# pca10028_connectors.net
KiCad netlist of a schematic drawn in Altium Designer
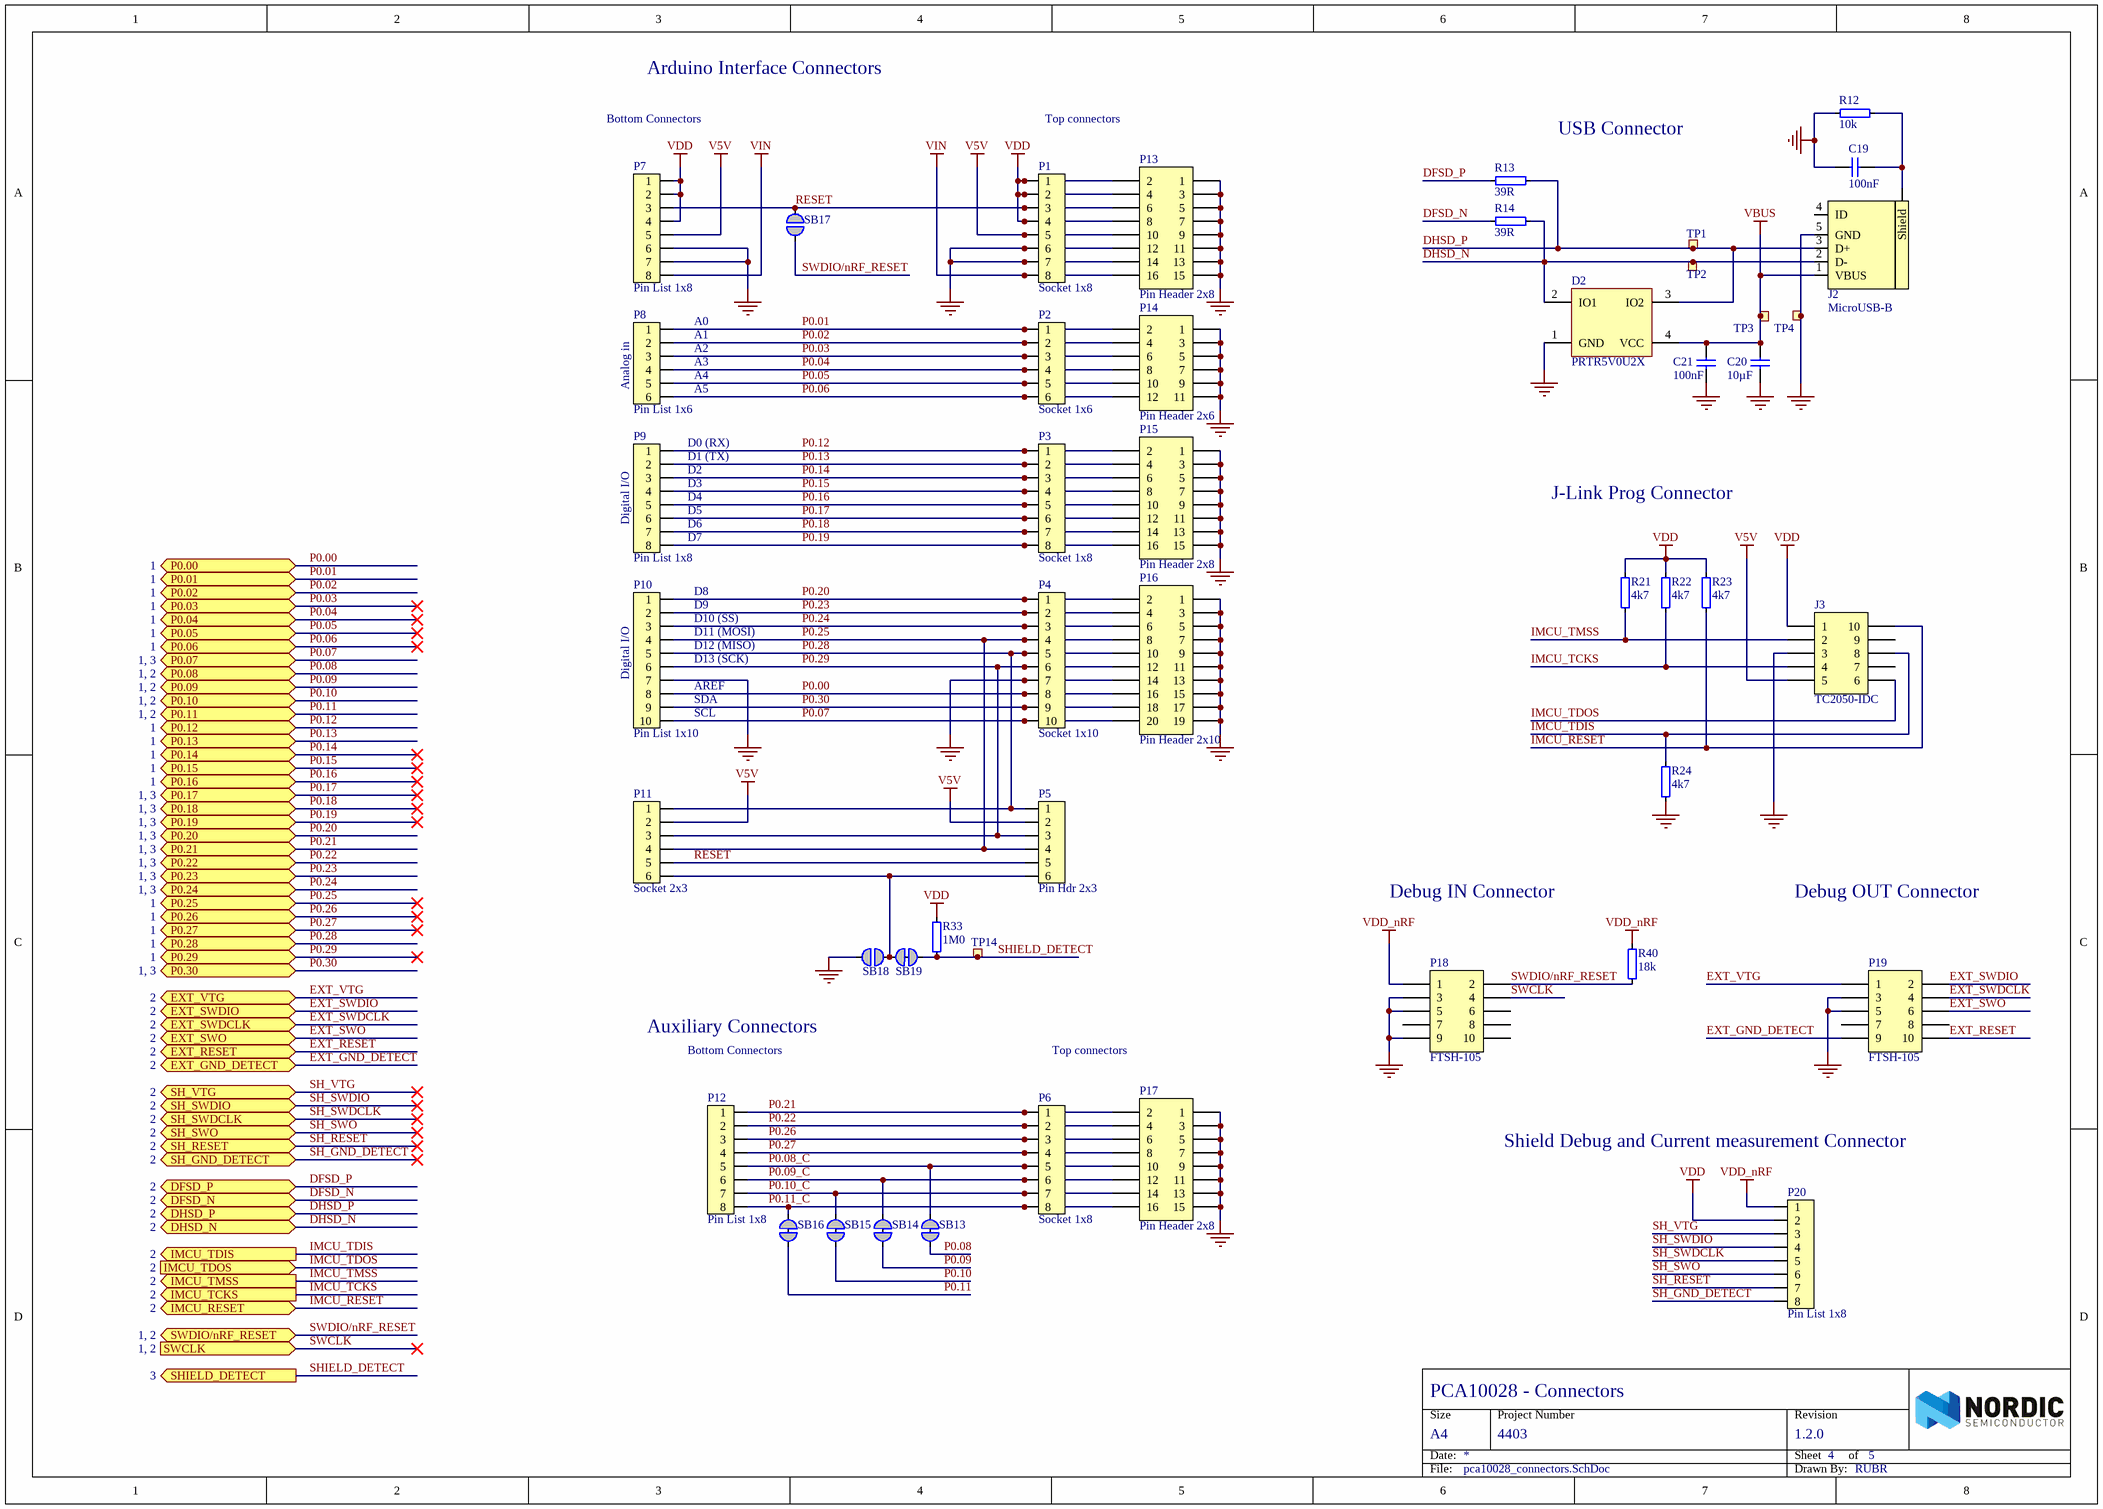
[diagram p0: pca10028_connectors.SchDoc]

(export (version "E")
  (design (tool "Eeschema 10.0.6"))
  (components
    (comp (ref "C19")
      (value "100nF")
      (footprint "CAPC1005X04L")
      (description "Capacitor, X7R, ±10%")
      (fields (field (name "PART NUMBER") "C0402-100n") (field (name "PUBLISHER") "Nordic Semiconductor"))
      (libsource (lib "Nordic Passive DB") (part "CAP"))
    )
    (comp (ref "C20")
      (value "10µF")
      (footprint "CAPC1608X06L")
      (description "Capacitor, X5R, ±20%")
      (fields (field (name "PART NUMBER") "C0603-10µ") (field (name "PUBLISHER") "Nordic Semiconductor"))
      (libsource (lib "Nordic Passive DB") (part "CAP"))
    )
    (comp (ref "C21")
      (value "100nF")
      (footprint "CAPC1005X04L")
      (description "Capacitor, X7R, ±10%")
      (fields (field (name "PART NUMBER") "C0402-100n") (field (name "PUBLISHER") "Nordic Semiconductor"))
      (libsource (lib "Nordic Passive DB") (part "CAP"))
    )
    (comp (ref "D2")
      (value "PRTR5V0U2X")
      (footprint "SOT190P230X110-4L")
      (description "Ultra low capacitance double rail-to-rail ESD protection diode")
      (fields
        (field (name "MANUFACTURER") "NXP")
        (field (name "2ND SOURCE PART NUMBER") "152-4157")
        (field (name "PUBLISHER") "Nordic Semiconductor")
      )
      (libsource (lib "Nordic Discrete DB") (part "PRTR5V0U2X"))
    )
    (comp (ref "J2")
      (value "MicroUSB-B")
      (footprint "FCI_10118193-0001LF")
      (description "MicroUSB-B-SMT")
      (fields
        (field (name "PART NUMBER") "FCI 10118193-0001LF")
        (field (name "MANUFACTURER") "FCI")
        (field (name "PUBLISHER") "Nordic Semiconductor")
      )
      (libsource (lib "Nordic Passive DB") (part "MiniUSB-AB-SMT"))
    )
    (comp (ref "J3")
      (value "TC2050-IDC")
      (footprint "TC2050-IDC-NLFP")
      (description "CBL PLUG-OF-NAILS 10-PIN")
      (fields
        (field (name "PART NUMBER") "TC2050-IDC-NLFP")
        (field (name "MANUFACTURER") "Tag-Connect LLC")
        (field (name "PUBLISHER") "Nordic Semiconductor")
      )
      (libsource (lib "Nordic Passive DB") (part "CONN-2x5_var2"))
    )
    (comp (ref "P1")
      (value "Socket 1x8")
      (footprint "SOCKET_1x8_SMD")
      (description "Socket 1x8, 2.54mm (100mil), SMD")
      (fields
        (field (name "PART NUMBER") "Socket 1x8 SMD")
        (field (name "MANUFACTURER") "Samtec")
        (field (name "PUBLISHER") "Nordic Semiconductor")
      )
      (libsource (lib "Nordic Passive DB") (part "CONN-8"))
    )
    (comp (ref "P2")
      (value "Socket 1x6")
      (footprint "SOCKET_1x6_SMD")
      (description "Socket 1x6, 2.54mm (100mil), SMD")
      (fields
        (field (name "PART NUMBER") "Socket 1x6 SMD")
        (field (name "MANUFACTURER") "Samtec")
        (field (name "PUBLISHER") "Nordic Semiconductor")
      )
      (libsource (lib "Nordic Passive DB") (part "CONN-6"))
    )
    (comp (ref "P3")
      (value "Socket 1x8")
      (footprint "SOCKET_1x8_SMD")
      (description "Socket 1x8, 2.54mm (100mil), SMD")
      (fields
        (field (name "PART NUMBER") "Socket 1x8 SMD")
        (field (name "MANUFACTURER") "Samtec")
        (field (name "PUBLISHER") "Nordic Semiconductor")
      )
      (libsource (lib "Nordic Passive DB") (part "CONN-8"))
    )
    (comp (ref "P4")
      (value "Socket 1x10")
      (footprint "SOCKET_1x10_SMD")
      (description "Socket 1x10, 2.54mm (100mil), SMD")
      (fields
        (field (name "PART NUMBER") "Socket 1x10 SMD")
        (field (name "MANUFACTURER") "Samtec")
        (field (name "PUBLISHER") "Nordic Semiconductor")
      )
      (libsource (lib "Nordic Passive DB") (part "CONN-10"))
    )
    (comp (ref "P5")
      (value "Pin Hdr 2x3")
      (footprint "Molex 15-91-2060")
      (description "Pin Header 2x3, 2.54mm (100mil) SMD")
      (fields
        (field (name "PART NUMBER") "Pin Header 2x3 SMD")
        (field (name "MANUFACTURER") "Molex")
        (field (name "PUBLISHER") "Nordic Semiconductor")
      )
      (libsource (lib "Nordic Passive DB") (part "CONN-6"))
    )
    (comp (ref "P6")
      (value "Socket 1x8")
      (footprint "SOCKET_1x8_SMD")
      (description "Socket 1x8, 2.54mm (100mil), SMD")
      (fields
        (field (name "PART NUMBER") "Socket 1x8 SMD")
        (field (name "MANUFACTURER") "Samtec")
        (field (name "PUBLISHER") "Nordic Semiconductor")
      )
      (libsource (lib "Nordic Passive DB") (part "CONN-8"))
    )
    (comp (ref "P7")
      (value "Pin List 1x8")
      (footprint "LIST_1x8_SMD")
      (description "Pin List 1x8, 2.54mm (100mil), SMD")
      (fields
        (field (name "PART NUMBER") "Pin List 1x8 SMD")
        (field (name "PUBLISHER") "Nordic Semiconductor")
      )
      (libsource (lib "") (part "CONN-8_1"))
    )
    (comp (ref "P8")
      (value "Pin List 1x6")
      (footprint "LIST_1x6_SMD")
      (description "Pin List 1x6, 2.54mm (100mil), SMD")
      (fields
        (field (name "PART NUMBER") "Pin List 1x6 SMD")
        (field (name "PUBLISHER") "Nordic Semiconductor")
      )
      (libsource (lib "") (part "CONN-6_1"))
    )
    (comp (ref "P9")
      (value "Pin List 1x8")
      (footprint "LIST_1x8_SMD")
      (description "Pin List 1x8, 2.54mm (100mil), SMD")
      (fields
        (field (name "PART NUMBER") "Pin List 1x8 SMD")
        (field (name "PUBLISHER") "Nordic Semiconductor")
      )
      (libsource (lib "") (part "CONN-8_1"))
    )
    (comp (ref "P10")
      (value "Pin List 1x10")
      (footprint "LIST_1x10_SMD")
      (description "Pin List 1x10, 2.54mm (100mil), SMD")
      (fields
        (field (name "PART NUMBER") "Pin List 1x10 SMD")
        (field (name "PUBLISHER") "Nordic Semiconductor")
      )
      (libsource (lib "") (part "CONN-10_1"))
    )
    (comp (ref "P11")
      (value "Socket 2x3")
      (footprint "SOCKET_2x3_SMD-2.54mm-bottom")
      (description "Socket 2x3, 2.54mm (100mil), SMD")
      (fields
        (field (name "PART NUMBER") "Socket 2x3 SMD Bottom")
        (field (name "MANUFACTURER") "Samtec")
        (field (name "PUBLISHER") "Nordic Semiconductor")
      )
      (libsource (lib "") (part "CONN-6_1"))
    )
    (comp (ref "P12")
      (value "Pin List 1x8")
      (footprint "LIST_1x8_SMD")
      (description "Pin List 1x8, 2.54mm (100mil), SMD")
      (fields
        (field (name "PART NUMBER") "Pin List 1x8 SMD")
        (field (name "PUBLISHER") "Nordic Semiconductor")
      )
      (libsource (lib "") (part "CONN-8_1"))
    )
    (comp (ref "P13")
      (value "Pin Header 2x8")
      (footprint "HDR_2x8")
      (description "Pin Header 2x8, 2.54mm (100mil)")
      (fields (field (name "PUBLISHER") "Nordic Semiconductor"))
      (libsource (lib "Nordic Passive DB") (part "CONN-2x8"))
    )
    (comp (ref "P14")
      (value "Pin Header 2x6")
      (footprint "HDR_2x6")
      (description "Pin Header 2x6, 2.54mm (100mil)")
      (fields (field (name "PUBLISHER") "Nordic Semiconductor"))
      (libsource (lib "Nordic Passive DB") (part "CONN-2x6"))
    )
    (comp (ref "P15")
      (value "Pin Header 2x8")
      (footprint "HDR_2x8")
      (description "Pin Header 2x8, 2.54mm (100mil)")
      (fields (field (name "PUBLISHER") "Nordic Semiconductor"))
      (libsource (lib "Nordic Passive DB") (part "CONN-2x8"))
    )
    (comp (ref "P16")
      (value "Pin Header 2x10")
      (footprint "HDR_2x10")
      (description "Pin Header 2x10, 2.54mm (100mil)")
      (fields (field (name "PUBLISHER") "Nordic Semiconductor"))
      (libsource (lib "Nordic Passive DB") (part "CONN-2x10"))
    )
    (comp (ref "P17")
      (value "Pin Header 2x8")
      (footprint "HDR_2x8")
      (description "Pin Header 2x8, 2.54mm (100mil)")
      (fields (field (name "PUBLISHER") "Nordic Semiconductor"))
      (libsource (lib "Nordic Passive DB") (part "CONN-2x8"))
    )
    (comp (ref "P18")
      (value "FTSH-105")
      (footprint "FTSH-105-K")
      (description "SAMTEC - CONN HEADER 10POS DUAL .05\" SMD KEYING SHROUD")
      (fields
        (field (name "PART NUMBER") "Samtec FTSH-105 Keying Shroud")
        (field (name "MANUFACTURER") "Samtec")
        (field (name "PUBLISHER") "Nordic Semiconductor")
      )
      (libsource (lib "Nordic Passive DB") (part "CONN-2x5"))
    )
    (comp (ref "P19")
      (value "FTSH-105")
      (footprint "FTSH-105-K")
      (description "SAMTEC - CONN HEADER 10POS DUAL .05\" SMD KEYING SHROUD")
      (fields
        (field (name "PART NUMBER") "Samtec FTSH-105 Keying Shroud")
        (field (name "MANUFACTURER") "Samtec")
        (field (name "PUBLISHER") "Nordic Semiconductor")
      )
      (libsource (lib "Nordic Passive DB") (part "CONN-2x5"))
    )
    (comp (ref "P20")
      (value "Pin List 1x8")
      (footprint "LIST_1x8_SMD")
      (description "Pin List 1x8, 2.54mm (100mil), SMD")
      (fields
        (field (name "PART NUMBER") "Pin List 1x8 SMD")
        (field (name "PUBLISHER") "Nordic Semiconductor")
      )
      (libsource (lib "Nordic Passive DB") (part "CONN-8"))
    )
    (comp (ref "R12")
      (value "10k")
      (footprint "RESC1005X04L")
      (description "Resistor, ±1%, 0.063W")
      (fields (field (name "PART NUMBER") "R0402-10k") (field (name "PUBLISHER") "Nordic Semiconductor"))
      (libsource (lib "Nordic Passive DB") (part "RES_1"))
    )
    (comp (ref "R13")
      (value "39R")
      (footprint "RESC1005X04L")
      (description "Resistor, ±1%, 0.063W")
      (fields (field (name "PART NUMBER") "R0402-39R") (field (name "PUBLISHER") "Nordic Semiconductor"))
      (libsource (lib "Nordic Passive DB") (part "RES_1"))
    )
    (comp (ref "R14")
      (value "39R")
      (footprint "RESC1005X04L")
      (description "Resistor, ±1%, 0.063W")
      (fields (field (name "PART NUMBER") "R0402-39R") (field (name "PUBLISHER") "Nordic Semiconductor"))
      (libsource (lib "Nordic Passive DB") (part "RES_1"))
    )
    (comp (ref "R21")
      (value "4k7")
      (footprint "RESC1005X04L")
      (description "Resistor, ±1%, 0.063W")
      (fields (field (name "PART NUMBER") "R0402-4k7") (field (name "PUBLISHER") "Nordic Semiconductor"))
      (libsource (lib "Nordic Passive DB") (part "RES_1"))
    )
    (comp (ref "R22")
      (value "4k7")
      (footprint "RESC1005X04L")
      (description "Resistor, ±1%, 0.063W")
      (fields (field (name "PART NUMBER") "R0402-4k7") (field (name "PUBLISHER") "Nordic Semiconductor"))
      (libsource (lib "Nordic Passive DB") (part "RES_1"))
    )
    (comp (ref "R23")
      (value "4k7")
      (footprint "RESC1005X04L")
      (description "Resistor, ±1%, 0.063W")
      (fields (field (name "PART NUMBER") "R0402-4k7") (field (name "PUBLISHER") "Nordic Semiconductor"))
      (libsource (lib "Nordic Passive DB") (part "RES_1"))
    )
    (comp (ref "R24")
      (value "4k7")
      (footprint "RESC1005X04L")
      (description "Resistor, ±1%, 0.063W")
      (fields (field (name "PART NUMBER") "R0402-4k7") (field (name "PUBLISHER") "Nordic Semiconductor"))
      (libsource (lib "Nordic Passive DB") (part "RES_1"))
    )
    (comp (ref "R33")
      (value "1M0")
      (footprint "RESC1005X04L")
      (description "Resistor, ±1%, 0.063W")
      (fields (field (name "PART NUMBER") "R0402-1M0") (field (name "PUBLISHER") "Nordic Semiconductor"))
      (libsource (lib "Nordic Passive DB") (part "RES_1"))
    )
    (comp (ref "R40")
      (value "18k")
      (footprint "RESC1005X04L")
      (description "Resistor, ±1%, 0.063W")
      (fields (field (name "PART NUMBER") "R0402-18k") (field (name "PUBLISHER") "Nordic Semiconductor"))
      (libsource (lib "Nordic Passive DB") (part "RES_1"))
    )
    (comp (ref "SB13")
      (value "Solderbridge")
      (footprint "Solderbridge_Shorted")
      (description "Shorted Solderbridge")
      (fields
        (field (name "PART NUMBER") "Solderbridge Shorted")
        (field (name "PUBLISHER") "Nordic Semiconductor")
      )
      (libsource (lib "Nordic Passive DB") (part "SOLDERBRIDGE_SHORTED"))
    )
    (comp (ref "SB14")
      (value "Solderbridge")
      (footprint "Solderbridge_Shorted")
      (description "Shorted Solderbridge")
      (fields
        (field (name "PART NUMBER") "Solderbridge Shorted")
        (field (name "PUBLISHER") "Nordic Semiconductor")
      )
      (libsource (lib "Nordic Passive DB") (part "SOLDERBRIDGE_SHORTED"))
    )
    (comp (ref "SB15")
      (value "Solderbridge")
      (footprint "Solderbridge_Shorted")
      (description "Shorted Solderbridge")
      (fields
        (field (name "PART NUMBER") "Solderbridge Shorted")
        (field (name "PUBLISHER") "Nordic Semiconductor")
      )
      (libsource (lib "Nordic Passive DB") (part "SOLDERBRIDGE_SHORTED"))
    )
    (comp (ref "SB16")
      (value "Solderbridge")
      (footprint "Solderbridge_Shorted")
      (description "Shorted Solderbridge")
      (fields
        (field (name "PART NUMBER") "Solderbridge Shorted")
        (field (name "PUBLISHER") "Nordic Semiconductor")
      )
      (libsource (lib "Nordic Passive DB") (part "SOLDERBRIDGE_SHORTED"))
    )
    (comp (ref "SB17")
      (value "Solderbridge")
      (footprint "Solderbridge")
      (fields (field (name "PUBLISHER") "Nordic Semiconductor"))
      (libsource (lib "Nordic Passive DB") (part "SOLDERBRIDGE"))
    )
    (comp (ref "SB18")
      (value "Solderbridge")
      (footprint "Solderbridge")
      (fields (field (name "PUBLISHER") "Nordic Semiconductor"))
      (libsource (lib "Nordic Passive DB") (part "SOLDERBRIDGE"))
    )
    (comp (ref "SB19")
      (value "Solderbridge")
      (footprint "Solderbridge_Shorted")
      (description "Shorted Solderbridge")
      (fields
        (field (name "PART NUMBER") "Solderbridge Shorted")
        (field (name "PUBLISHER") "Nordic Semiconductor")
      )
      (libsource (lib "Nordic Passive DB") (part "SOLDERBRIDGE_SHORTED"))
    )
    (comp (ref "TP1")
      (value "Ø1.0mm,SMD")
      (footprint "TP_SMD_Ø1.0mm")
      (description "1.0mm circular SMD testpad")
      (fields
        (field (name "PART NUMBER") "TP_SMD_Ø1.0MM")
        (field (name "MANUFACTURER") "Nordic Semiconductor")
        (field (name "PUBLISHER") "Nordic Semiconductor")
      )
      (libsource (lib "") (part "TESTPAD_1"))
    )
    (comp (ref "TP2")
      (value "Ø1.0mm,SMD")
      (footprint "TP_SMD_Ø1.0mm")
      (description "1.0mm circular SMD testpad")
      (fields
        (field (name "PART NUMBER") "TP_SMD_Ø1.0MM")
        (field (name "MANUFACTURER") "Nordic Semiconductor")
        (field (name "PUBLISHER") "Nordic Semiconductor")
      )
      (libsource (lib "Nordic Passive DB") (part "TESTPAD"))
    )
    (comp (ref "TP3")
      (value "Ø1.0mm,SMD")
      (footprint "TP_SMD_Ø1.0mm")
      (description "1.0mm circular SMD testpad")
      (fields
        (field (name "PART NUMBER") "TP_SMD_Ø1.0MM")
        (field (name "MANUFACTURER") "Nordic Semiconductor")
        (field (name "PUBLISHER") "Nordic Semiconductor")
      )
      (libsource (lib "") (part "TESTPAD_2"))
    )
    (comp (ref "TP4")
      (value "Ø1.0mm,SMD")
      (footprint "TP_SMD_Ø1.0mm")
      (description "1.0mm circular SMD testpad")
      (fields
        (field (name "PART NUMBER") "TP_SMD_Ø1.0MM")
        (field (name "MANUFACTURER") "Nordic Semiconductor")
        (field (name "PUBLISHER") "Nordic Semiconductor")
      )
      (libsource (lib "") (part "TESTPAD_3"))
    )
    (comp (ref "TP14")
      (value "Ø1.0mm,SMD")
      (footprint "TP_SMD_Ø1.0mm")
      (description "1.0mm circular SMD testpad")
      (fields
        (field (name "PART NUMBER") "TP_SMD_Ø1.0MM")
        (field (name "MANUFACTURER") "Nordic Semiconductor")
        (field (name "PUBLISHER") "Nordic Semiconductor")
      )
      (libsource (lib "") (part "TESTPAD_1"))
    )
  )
  (nets
    (net (code "1") (name "/DFSD_N") (class "Default")
      (node (ref "R14") (pin "1") (pinfunction "1_1") (pintype "passive"))
    )
    (net (code "2") (name "/DFSD_P") (class "Default")
      (node (ref "R13") (pin "1") (pinfunction "1_1") (pintype "passive"))
    )
    (net (code "3") (name "/DHSD_N") (class "Default")
      (node (ref "D2") (pin "2") (pinfunction "IO1_2") (pintype "passive"))
      (node (ref "J2") (pin "2") (pinfunction "D-_2") (pintype "passive"))
      (node (ref "R14") (pin "2") (pinfunction "2_2") (pintype "passive"))
      (node (ref "TP2") (pin "1") (pinfunction "1_1") (pintype "passive"))
    )
    (net (code "4") (name "/DHSD_P") (class "Default")
      (node (ref "D2") (pin "3") (pinfunction "IO2_3") (pintype "passive"))
      (node (ref "J2") (pin "3") (pinfunction "D+_3") (pintype "passive"))
      (node (ref "R13") (pin "2") (pinfunction "2_2") (pintype "passive"))
      (node (ref "TP1") (pin "1") (pinfunction "1_1") (pintype "passive"))
    )
    (net (code "5") (name "/EXT_GND_DETECT") (class "Default")
      (node (ref "P19") (pin "9") (pinfunction "9_9") (pintype "passive"))
    )
    (net (code "6") (name "/EXT_RESET") (class "Default")
      (node (ref "P19") (pin "10") (pinfunction "10_10") (pintype "passive"))
    )
    (net (code "7") (name "/EXT_SWDCLK") (class "Default")
      (node (ref "P19") (pin "4") (pinfunction "4_4") (pintype "passive"))
    )
    (net (code "8") (name "/EXT_SWDIO") (class "Default")
      (node (ref "P19") (pin "2") (pinfunction "2_2") (pintype "passive"))
    )
    (net (code "9") (name "/EXT_SWO") (class "Default")
      (node (ref "P19") (pin "6") (pinfunction "6_6") (pintype "passive"))
    )
    (net (code "10") (name "/EXT_VTG") (class "Default")
      (node (ref "P19") (pin "1") (pinfunction "1_1") (pintype "passive"))
    )
    (net (code "11") (name "/IMCU_RESET") (class "Default")
      (node (ref "J3") (pin "10") (pinfunction "10_10") (pintype "passive"))
      (node (ref "R23") (pin "1") (pinfunction "1_1") (pintype "passive"))
    )
    (net (code "12") (name "/IMCU_TCKS") (class "Default")
      (node (ref "J3") (pin "4") (pinfunction "4_4") (pintype "passive"))
      (node (ref "R22") (pin "1") (pinfunction "1_1") (pintype "passive"))
    )
    (net (code "13") (name "/IMCU_TDIS") (class "Default")
      (node (ref "J3") (pin "8") (pinfunction "8_8") (pintype "passive"))
      (node (ref "R24") (pin "1") (pinfunction "1_1") (pintype "passive"))
    )
    (net (code "14") (name "/IMCU_TDOS") (class "Default")
      (node (ref "J3") (pin "6") (pinfunction "6_6") (pintype "passive"))
    )
    (net (code "15") (name "/IMCU_TMSS") (class "Default")
      (node (ref "J3") (pin "2") (pinfunction "2_2") (pintype "passive"))
      (node (ref "R21") (pin "1") (pinfunction "1_1") (pintype "passive"))
    )
    (net (code "16") (name "/P0.00") (class "Default")
      (node (ref "P10") (pin "8") (pinfunction "8_8") (pintype "passive"))
      (node (ref "P16") (pin "16") (pinfunction "16_16") (pintype "passive"))
      (node (ref "P4") (pin "8") (pinfunction "8_8") (pintype "passive"))
    )
    (net (code "17") (name "/P0.01") (class "Default")
      (node (ref "P14") (pin "2") (pinfunction "2_2") (pintype "passive"))
      (node (ref "P2") (pin "1") (pinfunction "1_1") (pintype "passive"))
      (node (ref "P8") (pin "1") (pinfunction "1_1") (pintype "passive"))
    )
    (net (code "18") (name "/P0.02") (class "Default")
      (node (ref "P14") (pin "4") (pinfunction "4_4") (pintype "passive"))
      (node (ref "P2") (pin "2") (pinfunction "2_2") (pintype "passive"))
      (node (ref "P8") (pin "2") (pinfunction "2_2") (pintype "passive"))
    )
    (net (code "19") (name "/P0.03") (class "Default")
      (node (ref "P14") (pin "6") (pinfunction "6_6") (pintype "passive"))
      (node (ref "P2") (pin "3") (pinfunction "3_3") (pintype "power_in"))
      (node (ref "P8") (pin "3") (pinfunction "3_3") (pintype "power_in"))
    )
    (net (code "20") (name "/P0.04") (class "Default")
      (node (ref "P14") (pin "8") (pinfunction "8_8") (pintype "passive"))
      (node (ref "P2") (pin "4") (pinfunction "4_4") (pintype "power_in"))
      (node (ref "P8") (pin "4") (pinfunction "4_4") (pintype "power_in"))
    )
    (net (code "21") (name "/P0.05") (class "Default")
      (node (ref "P14") (pin "10") (pinfunction "10_10") (pintype "passive"))
      (node (ref "P2") (pin "5") (pinfunction "5_5") (pintype "power_in"))
      (node (ref "P8") (pin "5") (pinfunction "5_5") (pintype "power_in"))
    )
    (net (code "22") (name "/P0.06") (class "Default")
      (node (ref "P14") (pin "12") (pinfunction "12_12") (pintype "passive"))
      (node (ref "P2") (pin "6") (pinfunction "6_6") (pintype "power_in"))
      (node (ref "P8") (pin "6") (pinfunction "6_6") (pintype "power_in"))
    )
    (net (code "23") (name "/P0.07") (class "Default")
      (node (ref "P10") (pin "10") (pinfunction "10_10") (pintype "passive"))
      (node (ref "P16") (pin "20") (pinfunction "20_20") (pintype "passive"))
      (node (ref "P4") (pin "10") (pinfunction "10_10") (pintype "passive"))
    )
    (net (code "24") (name "/P0.08") (class "Default")
      (node (ref "SB13") (pin "2") (pinfunction "1_2") (pintype "passive"))
    )
    (net (code "25") (name "/P0.08_C") (class "Default")
      (node (ref "P12") (pin "5") (pinfunction "5_5") (pintype "power_in"))
      (node (ref "P17") (pin "10") (pinfunction "10_10") (pintype "passive"))
      (node (ref "P6") (pin "5") (pinfunction "5_5") (pintype "power_in"))
      (node (ref "SB13") (pin "1") (pinfunction "0_1") (pintype "passive"))
    )
    (net (code "26") (name "/P0.09") (class "Default")
      (node (ref "SB14") (pin "2") (pinfunction "1_2") (pintype "passive"))
    )
    (net (code "27") (name "/P0.09_C") (class "Default")
      (node (ref "P12") (pin "6") (pinfunction "6_6") (pintype "power_in"))
      (node (ref "P17") (pin "12") (pinfunction "12_12") (pintype "passive"))
      (node (ref "P6") (pin "6") (pinfunction "6_6") (pintype "power_in"))
      (node (ref "SB14") (pin "1") (pinfunction "0_1") (pintype "passive"))
    )
    (net (code "28") (name "/P0.10") (class "Default")
      (node (ref "SB15") (pin "2") (pinfunction "1_2") (pintype "passive"))
    )
    (net (code "29") (name "/P0.10_C") (class "Default")
      (node (ref "P12") (pin "7") (pinfunction "7_7") (pintype "power_in"))
      (node (ref "P17") (pin "14") (pinfunction "14_14") (pintype "passive"))
      (node (ref "P6") (pin "7") (pinfunction "7_7") (pintype "power_in"))
      (node (ref "SB15") (pin "1") (pinfunction "0_1") (pintype "passive"))
    )
    (net (code "30") (name "/P0.11") (class "Default")
      (node (ref "SB16") (pin "2") (pinfunction "1_2") (pintype "passive"))
    )
    (net (code "31") (name "/P0.11_C") (class "Default")
      (node (ref "P12") (pin "8") (pinfunction "8_8") (pintype "power_in"))
      (node (ref "P17") (pin "16") (pinfunction "16_16") (pintype "passive"))
      (node (ref "P6") (pin "8") (pinfunction "8_8") (pintype "power_in"))
      (node (ref "SB16") (pin "1") (pinfunction "0_1") (pintype "passive"))
    )
    (net (code "32") (name "/P0.12") (class "Default")
      (node (ref "P15") (pin "2") (pinfunction "2_2") (pintype "passive"))
      (node (ref "P3") (pin "1") (pinfunction "1_1") (pintype "passive"))
      (node (ref "P9") (pin "1") (pinfunction "1_1") (pintype "passive"))
    )
    (net (code "33") (name "/P0.13") (class "Default")
      (node (ref "P15") (pin "4") (pinfunction "4_4") (pintype "passive"))
      (node (ref "P3") (pin "2") (pinfunction "2_2") (pintype "passive"))
      (node (ref "P9") (pin "2") (pinfunction "2_2") (pintype "passive"))
    )
    (net (code "34") (name "/P0.14") (class "Default")
      (node (ref "P15") (pin "6") (pinfunction "6_6") (pintype "passive"))
      (node (ref "P3") (pin "3") (pinfunction "3_3") (pintype "power_in"))
      (node (ref "P9") (pin "3") (pinfunction "3_3") (pintype "power_in"))
    )
    (net (code "35") (name "/P0.15") (class "Default")
      (node (ref "P15") (pin "8") (pinfunction "8_8") (pintype "passive"))
      (node (ref "P3") (pin "4") (pinfunction "4_4") (pintype "power_in"))
      (node (ref "P9") (pin "4") (pinfunction "4_4") (pintype "power_in"))
    )
    (net (code "36") (name "/P0.16") (class "Default")
      (node (ref "P15") (pin "10") (pinfunction "10_10") (pintype "passive"))
      (node (ref "P3") (pin "5") (pinfunction "5_5") (pintype "power_in"))
      (node (ref "P9") (pin "5") (pinfunction "5_5") (pintype "power_in"))
    )
    (net (code "37") (name "/P0.17") (class "Default")
      (node (ref "P15") (pin "12") (pinfunction "12_12") (pintype "passive"))
      (node (ref "P3") (pin "6") (pinfunction "6_6") (pintype "power_in"))
      (node (ref "P9") (pin "6") (pinfunction "6_6") (pintype "power_in"))
    )
    (net (code "38") (name "/P0.18") (class "Default")
      (node (ref "P15") (pin "14") (pinfunction "14_14") (pintype "passive"))
      (node (ref "P3") (pin "7") (pinfunction "7_7") (pintype "power_in"))
      (node (ref "P9") (pin "7") (pinfunction "7_7") (pintype "power_in"))
    )
    (net (code "39") (name "/P0.19") (class "Default")
      (node (ref "P15") (pin "16") (pinfunction "16_16") (pintype "passive"))
      (node (ref "P3") (pin "8") (pinfunction "8_8") (pintype "power_in"))
      (node (ref "P9") (pin "8") (pinfunction "8_8") (pintype "power_in"))
    )
    (net (code "40") (name "/P0.20") (class "Default")
      (node (ref "P10") (pin "1") (pinfunction "1_1") (pintype "passive"))
      (node (ref "P16") (pin "2") (pinfunction "2_2") (pintype "passive"))
      (node (ref "P4") (pin "1") (pinfunction "1_1") (pintype "passive"))
    )
    (net (code "41") (name "/P0.21") (class "Default")
      (node (ref "P12") (pin "1") (pinfunction "1_1") (pintype "passive"))
      (node (ref "P17") (pin "2") (pinfunction "2_2") (pintype "passive"))
      (node (ref "P6") (pin "1") (pinfunction "1_1") (pintype "passive"))
    )
    (net (code "42") (name "/P0.22") (class "Default")
      (node (ref "P12") (pin "2") (pinfunction "2_2") (pintype "passive"))
      (node (ref "P17") (pin "4") (pinfunction "4_4") (pintype "passive"))
      (node (ref "P6") (pin "2") (pinfunction "2_2") (pintype "passive"))
    )
    (net (code "43") (name "/P0.23") (class "Default")
      (node (ref "P10") (pin "2") (pinfunction "2_2") (pintype "passive"))
      (node (ref "P16") (pin "4") (pinfunction "4_4") (pintype "passive"))
      (node (ref "P4") (pin "2") (pinfunction "2_2") (pintype "passive"))
    )
    (net (code "44") (name "/P0.24") (class "Default")
      (node (ref "P10") (pin "3") (pinfunction "3_3") (pintype "passive"))
      (node (ref "P16") (pin "6") (pinfunction "6_6") (pintype "passive"))
      (node (ref "P4") (pin "3") (pinfunction "3_3") (pintype "passive"))
    )
    (net (code "45") (name "/P0.25") (class "Default")
      (node (ref "P10") (pin "4") (pinfunction "4_4") (pintype "passive"))
      (node (ref "P11") (pin "4") (pinfunction "4_4") (pintype "power_in"))
      (node (ref "P16") (pin "8") (pinfunction "8_8") (pintype "passive"))
      (node (ref "P4") (pin "4") (pinfunction "4_4") (pintype "passive"))
      (node (ref "P5") (pin "4") (pinfunction "4_4") (pintype "power_in"))
    )
    (net (code "46") (name "/P0.26") (class "Default")
      (node (ref "P12") (pin "3") (pinfunction "3_3") (pintype "power_in"))
      (node (ref "P17") (pin "6") (pinfunction "6_6") (pintype "passive"))
      (node (ref "P6") (pin "3") (pinfunction "3_3") (pintype "power_in"))
    )
    (net (code "47") (name "/P0.27") (class "Default")
      (node (ref "P12") (pin "4") (pinfunction "4_4") (pintype "power_in"))
      (node (ref "P17") (pin "8") (pinfunction "8_8") (pintype "passive"))
      (node (ref "P6") (pin "4") (pinfunction "4_4") (pintype "power_in"))
    )
    (net (code "48") (name "/P0.28") (class "Default")
      (node (ref "P10") (pin "5") (pinfunction "5_5") (pintype "passive"))
      (node (ref "P11") (pin "1") (pinfunction "1_1") (pintype "passive"))
      (node (ref "P16") (pin "10") (pinfunction "10_10") (pintype "passive"))
      (node (ref "P4") (pin "5") (pinfunction "5_5") (pintype "passive"))
      (node (ref "P5") (pin "1") (pinfunction "1_1") (pintype "passive"))
    )
    (net (code "49") (name "/P0.29") (class "Default")
      (node (ref "P10") (pin "6") (pinfunction "6_6") (pintype "passive"))
      (node (ref "P11") (pin "3") (pinfunction "3_3") (pintype "power_in"))
      (node (ref "P16") (pin "12") (pinfunction "12_12") (pintype "passive"))
      (node (ref "P4") (pin "6") (pinfunction "6_6") (pintype "passive"))
      (node (ref "P5") (pin "3") (pinfunction "3_3") (pintype "power_in"))
    )
    (net (code "50") (name "/P0.30") (class "Default")
      (node (ref "P10") (pin "9") (pinfunction "9_9") (pintype "passive"))
      (node (ref "P16") (pin "18") (pinfunction "18_18") (pintype "passive"))
      (node (ref "P4") (pin "9") (pinfunction "9_9") (pintype "passive"))
    )
    (net (code "51") (name "/RESET") (class "Default")
      (node (ref "P1") (pin "3") (pinfunction "3_3") (pintype "power_in"))
      (node (ref "P11") (pin "5") (pinfunction "5_5") (pintype "power_in"))
      (node (ref "P13") (pin "6") (pinfunction "6_6") (pintype "passive"))
      (node (ref "P5") (pin "5") (pinfunction "5_5") (pintype "power_in"))
      (node (ref "P7") (pin "3") (pinfunction "3_3") (pintype "power_in"))
      (node (ref "SB17") (pin "1") (pinfunction "0_1") (pintype "passive"))
    )
    (net (code "52") (name "/SHIELD_DETECT") (class "Default")
      (node (ref "R33") (pin "1") (pinfunction "1_1") (pintype "passive"))
      (node (ref "SB19") (pin "2") (pinfunction "1_2") (pintype "passive"))
      (node (ref "TP14") (pin "1") (pinfunction "1_1") (pintype "passive"))
    )
    (net (code "53") (name "/SH_GND_DETECT") (class "Default")
      (node (ref "P20") (pin "8") (pinfunction "8_8") (pintype "power_in+no_connect"))
    )
    (net (code "54") (name "/SH_RESET") (class "Default")
      (node (ref "P20") (pin "7") (pinfunction "7_7") (pintype "power_in+no_connect"))
    )
    (net (code "55") (name "/SH_SWDCLK") (class "Default")
      (node (ref "P20") (pin "5") (pinfunction "5_5") (pintype "power_in+no_connect"))
    )
    (net (code "56") (name "/SH_SWDIO") (class "Default")
      (node (ref "P20") (pin "4") (pinfunction "4_4") (pintype "power_in+no_connect"))
    )
    (net (code "57") (name "/SH_SWO") (class "Default")
      (node (ref "P20") (pin "6") (pinfunction "6_6") (pintype "power_in+no_connect"))
    )
    (net (code "58") (name "/SH_VTG") (class "Default")
      (node (ref "P20") (pin "3") (pinfunction "3_3") (pintype "power_in+no_connect"))
    )
    (net (code "59") (name "/SWCLK") (class "Default")
      (node (ref "P18") (pin "4") (pinfunction "4_4") (pintype "passive+no_connect"))
    )
    (net (code "60") (name "/SWDIO{slash}nRF_RESET") (class "Default")
      (node (ref "P18") (pin "2") (pinfunction "2_2") (pintype "passive"))
      (node (ref "R40") (pin "1") (pinfunction "1_1") (pintype "passive"))
      (node (ref "SB17") (pin "2") (pinfunction "1_2") (pintype "passive"))
    )
    (net (code "61") (name "GND") (class "Default")
      (node (ref "C19") (pin "1") (pinfunction "1_1") (pintype "passive"))
      (node (ref "C20") (pin "1") (pinfunction "1_1") (pintype "passive"))
      (node (ref "C21") (pin "1") (pinfunction "1_1") (pintype "passive"))
      (node (ref "D2") (pin "1") (pinfunction "GND_1") (pintype "passive"))
      (node (ref "J2") (pin "5") (pinfunction "GND_5") (pintype "power_in"))
      (node (ref "J3") (pin "3") (pinfunction "3_3") (pintype "passive"))
      (node (ref "P1") (pin "6") (pinfunction "6_6") (pintype "power_in"))
      (node (ref "P1") (pin "7") (pinfunction "7_7") (pintype "power_in"))
      (node (ref "P10") (pin "7") (pinfunction "7_7") (pintype "passive"))
      (node (ref "P13") (pin "1") (pinfunction "1_1") (pintype "passive"))
      (node (ref "P13") (pin "11") (pinfunction "11_11") (pintype "passive"))
      (node (ref "P13") (pin "12") (pinfunction "12_12") (pintype "passive"))
      (node (ref "P13") (pin "13") (pinfunction "13_13") (pintype "passive"))
      (node (ref "P13") (pin "14") (pinfunction "14_14") (pintype "passive"))
      (node (ref "P13") (pin "15") (pinfunction "15_15") (pintype "passive"))
      (node (ref "P13") (pin "3") (pinfunction "3_3") (pintype "passive"))
      (node (ref "P13") (pin "5") (pinfunction "5_5") (pintype "passive"))
      (node (ref "P13") (pin "7") (pinfunction "7_7") (pintype "passive"))
      (node (ref "P13") (pin "9") (pinfunction "9_9") (pintype "passive"))
      (node (ref "P14") (pin "1") (pinfunction "1_1") (pintype "passive"))
      (node (ref "P14") (pin "11") (pinfunction "11_11") (pintype "passive"))
      (node (ref "P14") (pin "3") (pinfunction "3_3") (pintype "passive"))
      (node (ref "P14") (pin "5") (pinfunction "5_5") (pintype "passive"))
      (node (ref "P14") (pin "7") (pinfunction "7_7") (pintype "passive"))
      (node (ref "P14") (pin "9") (pinfunction "9_9") (pintype "passive"))
      (node (ref "P15") (pin "1") (pinfunction "1_1") (pintype "passive"))
      (node (ref "P15") (pin "11") (pinfunction "11_11") (pintype "passive"))
      (node (ref "P15") (pin "13") (pinfunction "13_13") (pintype "passive"))
      (node (ref "P15") (pin "15") (pinfunction "15_15") (pintype "passive"))
      (node (ref "P15") (pin "3") (pinfunction "3_3") (pintype "passive"))
      (node (ref "P15") (pin "5") (pinfunction "5_5") (pintype "passive"))
      (node (ref "P15") (pin "7") (pinfunction "7_7") (pintype "passive"))
      (node (ref "P15") (pin "9") (pinfunction "9_9") (pintype "passive"))
      (node (ref "P16") (pin "1") (pinfunction "1_1") (pintype "passive"))
      (node (ref "P16") (pin "11") (pinfunction "11_11") (pintype "passive"))
      (node (ref "P16") (pin "13") (pinfunction "13_13") (pintype "passive"))
      (node (ref "P16") (pin "14") (pinfunction "14_14") (pintype "passive"))
      (node (ref "P16") (pin "15") (pinfunction "15_15") (pintype "passive"))
      (node (ref "P16") (pin "17") (pinfunction "17_17") (pintype "passive"))
      (node (ref "P16") (pin "19") (pinfunction "19_19") (pintype "passive"))
      (node (ref "P16") (pin "3") (pinfunction "3_3") (pintype "passive"))
      (node (ref "P16") (pin "5") (pinfunction "5_5") (pintype "passive"))
      (node (ref "P16") (pin "7") (pinfunction "7_7") (pintype "passive"))
      (node (ref "P16") (pin "9") (pinfunction "9_9") (pintype "passive"))
      (node (ref "P17") (pin "1") (pinfunction "1_1") (pintype "passive"))
      (node (ref "P17") (pin "11") (pinfunction "11_11") (pintype "passive"))
      (node (ref "P17") (pin "13") (pinfunction "13_13") (pintype "passive"))
      (node (ref "P17") (pin "15") (pinfunction "15_15") (pintype "passive"))
      (node (ref "P17") (pin "3") (pinfunction "3_3") (pintype "passive"))
      (node (ref "P17") (pin "5") (pinfunction "5_5") (pintype "passive"))
      (node (ref "P17") (pin "7") (pinfunction "7_7") (pintype "passive"))
      (node (ref "P17") (pin "9") (pinfunction "9_9") (pintype "passive"))
      (node (ref "P18") (pin "3") (pinfunction "3_3") (pintype "passive"))
      (node (ref "P18") (pin "5") (pinfunction "5_5") (pintype "passive"))
      (node (ref "P18") (pin "9") (pinfunction "9_9") (pintype "passive"))
      (node (ref "P19") (pin "3") (pinfunction "3_3") (pintype "passive"))
      (node (ref "P19") (pin "5") (pinfunction "5_5") (pintype "passive"))
      (node (ref "P4") (pin "7") (pinfunction "7_7") (pintype "passive"))
      (node (ref "P7") (pin "6") (pinfunction "6_6") (pintype "power_in"))
      (node (ref "P7") (pin "7") (pinfunction "7_7") (pintype "power_in"))
      (node (ref "R12") (pin "1") (pinfunction "1_1") (pintype "passive"))
      (node (ref "R24") (pin "2") (pinfunction "2_2") (pintype "passive"))
      (node (ref "SB18") (pin "1") (pinfunction "0_1") (pintype "passive"))
      (node (ref "TP4") (pin "1") (pinfunction "1_1") (pintype "passive"))
    )
    (net (code "62") (name "Net-(J2-Shield)") (class "Default")
      (node (ref "C19") (pin "2") (pinfunction "2_2") (pintype "passive"))
      (node (ref "J2") (pin "6") (pinfunction "Shield_6") (pintype "power_in"))
      (node (ref "R12") (pin "2") (pinfunction "2_2") (pintype "passive"))
    )
    (net (code "63") (name "Net-(SB18-1)") (class "Default")
      (node (ref "P11") (pin "6") (pinfunction "6_6") (pintype "power_in"))
      (node (ref "P5") (pin "6") (pinfunction "6_6") (pintype "power_in"))
      (node (ref "SB18") (pin "2") (pinfunction "1_2") (pintype "passive"))
      (node (ref "SB19") (pin "1") (pinfunction "0_1") (pintype "passive"))
    )
    (net (code "64") (name "V5V") (class "Default")
      (node (ref "J3") (pin "5") (pinfunction "5_5") (pintype "passive"))
      (node (ref "P1") (pin "5") (pinfunction "5_5") (pintype "power_in"))
      (node (ref "P11") (pin "2") (pinfunction "2_2") (pintype "passive"))
      (node (ref "P13") (pin "10") (pinfunction "10_10") (pintype "passive"))
      (node (ref "P5") (pin "2") (pinfunction "2_2") (pintype "passive"))
      (node (ref "P7") (pin "5") (pinfunction "5_5") (pintype "power_in"))
    )
    (net (code "65") (name "VBUS") (class "Default")
      (node (ref "C20") (pin "2") (pinfunction "2_2") (pintype "passive"))
      (node (ref "C21") (pin "2") (pinfunction "2_2") (pintype "passive"))
      (node (ref "D2") (pin "4") (pinfunction "VCC_4") (pintype "passive"))
      (node (ref "J2") (pin "1") (pinfunction "VBUS_1") (pintype "power_in"))
      (node (ref "TP3") (pin "1") (pinfunction "1_1") (pintype "passive"))
    )
    (net (code "66") (name "VDD") (class "Default")
      (node (ref "J3") (pin "1") (pinfunction "1_1") (pintype "passive"))
      (node (ref "P1") (pin "1") (pinfunction "1_1") (pintype "passive"))
      (node (ref "P1") (pin "2") (pinfunction "2_2") (pintype "passive"))
      (node (ref "P1") (pin "4") (pinfunction "4_4") (pintype "power_in"))
      (node (ref "P13") (pin "2") (pinfunction "2_2") (pintype "passive"))
      (node (ref "P13") (pin "4") (pinfunction "4_4") (pintype "passive"))
      (node (ref "P13") (pin "8") (pinfunction "8_8") (pintype "passive"))
      (node (ref "P20") (pin "2") (pinfunction "2_2") (pintype "passive"))
      (node (ref "P7") (pin "1") (pinfunction "1_1") (pintype "passive"))
      (node (ref "P7") (pin "2") (pinfunction "2_2") (pintype "passive"))
      (node (ref "P7") (pin "4") (pinfunction "4_4") (pintype "power_in"))
      (node (ref "R21") (pin "2") (pinfunction "2_2") (pintype "passive"))
      (node (ref "R22") (pin "2") (pinfunction "2_2") (pintype "passive"))
      (node (ref "R23") (pin "2") (pinfunction "2_2") (pintype "passive"))
      (node (ref "R33") (pin "2") (pinfunction "2_2") (pintype "passive"))
    )
    (net (code "67") (name "VDD_nRF") (class "Default")
      (node (ref "P18") (pin "1") (pinfunction "1_1") (pintype "passive"))
      (node (ref "P20") (pin "1") (pinfunction "1_1") (pintype "passive"))
      (node (ref "R40") (pin "2") (pinfunction "2_2") (pintype "passive"))
    )
    (net (code "68") (name "VIN") (class "Default")
      (node (ref "P1") (pin "8") (pinfunction "8_8") (pintype "power_in"))
      (node (ref "P13") (pin "16") (pinfunction "16_16") (pintype "passive"))
      (node (ref "P7") (pin "8") (pinfunction "8_8") (pintype "power_in"))
    )
    (net (code "69") (name "unconnected-(J2-ID-Pad4)") (class "Default")
      (node (ref "J2") (pin "4") (pinfunction "ID_4") (pintype "passive"))
    )
    (net (code "70") (name "unconnected-(J3-Pad7)") (class "Default")
      (node (ref "J3") (pin "7") (pinfunction "7_7") (pintype "passive"))
    )
    (net (code "71") (name "unconnected-(J3-Pad9)") (class "Default")
      (node (ref "J3") (pin "9") (pinfunction "9_9") (pintype "passive"))
    )
    (net (code "72") (name "unconnected-(P18-Pad6)") (class "Default")
      (node (ref "P18") (pin "6") (pinfunction "6_6") (pintype "passive"))
    )
    (net (code "73") (name "unconnected-(P18-Pad7)") (class "Default")
      (node (ref "P18") (pin "7") (pinfunction "7_7") (pintype "passive"))
    )
    (net (code "74") (name "unconnected-(P18-Pad8)") (class "Default")
      (node (ref "P18") (pin "8") (pinfunction "8_8") (pintype "passive"))
    )
    (net (code "75") (name "unconnected-(P18-Pad10)") (class "Default")
      (node (ref "P18") (pin "10") (pinfunction "10_10") (pintype "passive"))
    )
    (net (code "76") (name "unconnected-(P19-Pad7)") (class "Default")
      (node (ref "P19") (pin "7") (pinfunction "7_7") (pintype "passive"))
    )
    (net (code "77") (name "unconnected-(P19-Pad8)") (class "Default")
      (node (ref "P19") (pin "8") (pinfunction "8_8") (pintype "passive"))
    )
  )
)
